# MBC5_1-3_multi.net
KiCad netlist of a schematic drawn in EAGLE
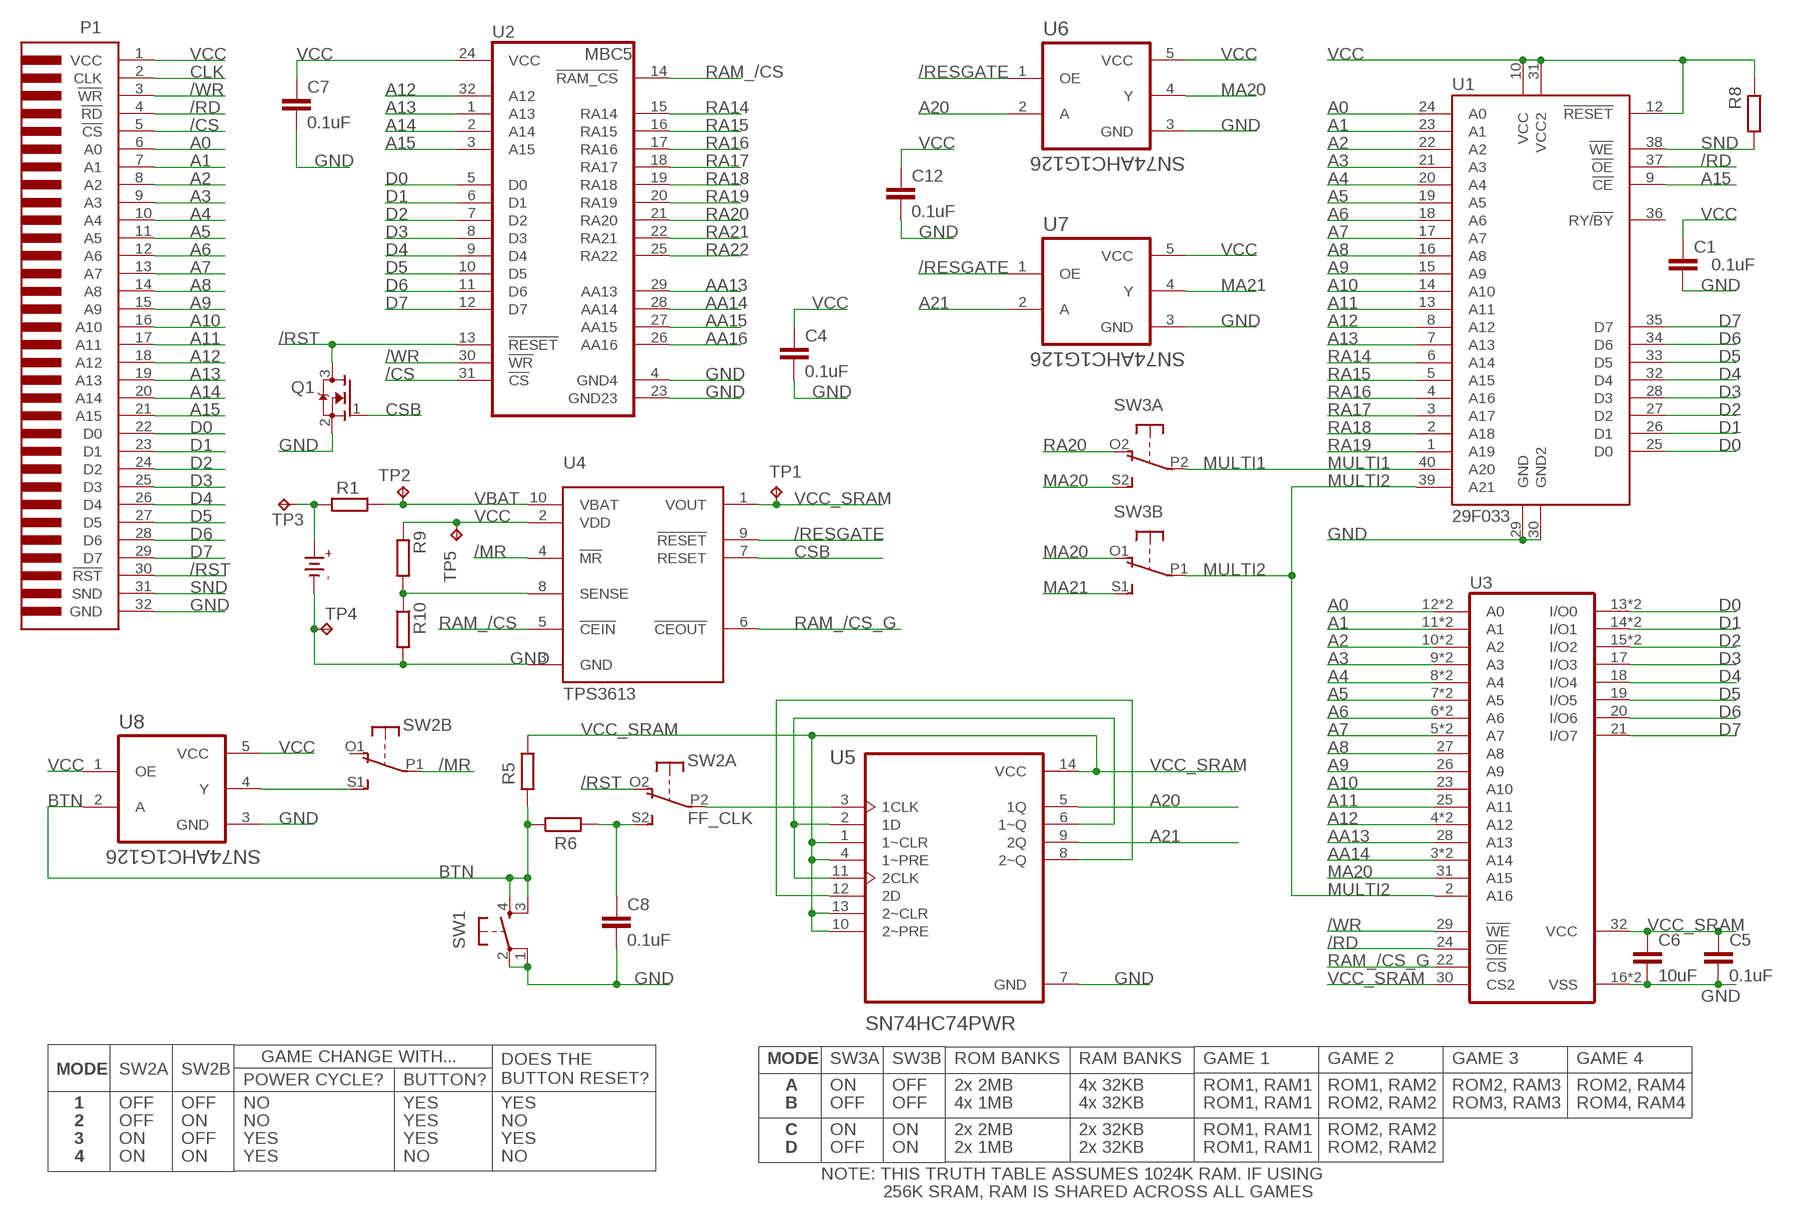
[diagram p0: schematic, sheet 1]

(export (version "E")
  (design (tool "Eeschema 10.0.6"))
  (components
    (comp (ref "C1")
      (value "0.1uF")
      (footprint "eagle-import:C0603")
      (libsource (lib "eagle-import") (part "C-EUC0603"))
    )
    (comp (ref "C4")
      (value "0.1uF")
      (footprint "eagle-import:C0603")
      (libsource (lib "eagle-import") (part "C-EUC0603"))
    )
    (comp (ref "C5")
      (value "0.1uF")
      (footprint "eagle-import:C0603")
      (libsource (lib "eagle-import") (part "C-EUC0603"))
    )
    (comp (ref "C6")
      (value "10uF")
      (footprint "eagle-import:C0603")
      (libsource (lib "eagle-import") (part "C-EUC0603"))
    )
    (comp (ref "C7")
      (value "0.1uF")
      (footprint "eagle-import:C0603")
      (libsource (lib "eagle-import") (part "C-EUC0603"))
    )
    (comp (ref "C8")
      (value "0.1uF")
      (footprint "eagle-import:C0603")
      (libsource (lib "eagle-import") (part "C-EUC0603"))
    )
    (comp (ref "C12")
      (value "0.1uF")
      (footprint "eagle-import:C0603")
      (libsource (lib "eagle-import") (part "C-EUC0603"))
    )
    (comp (ref "P1")
      (value "GBC_CARTTAB")
      (footprint "eagle-import:GBC_CART_TABBED")
      (libsource (lib "eagle-import") (part "GBC_CARTTAB"))
    )
    (comp (ref "Q1")
      (value "2N7002")
      (footprint "eagle-import:SOT23")
      (libsource (lib "eagle-import") (part "MOSFET-NREFLOW"))
    )
    (comp (ref "R1")
      (value "RR0603")
      (footprint "eagle-import:R0603")
      (libsource (lib "eagle-import") (part "RR0603"))
    )
    (comp (ref "R5")
      (value "RR0603")
      (footprint "eagle-import:R0603")
      (libsource (lib "eagle-import") (part "RR0603"))
    )
    (comp (ref "R6")
      (value "RR0603")
      (footprint "eagle-import:R0603")
      (libsource (lib "eagle-import") (part "RR0603"))
    )
    (comp (ref "R8")
      (value "RR0603")
      (footprint "eagle-import:R0603")
      (libsource (lib "eagle-import") (part "RR0603"))
    )
    (comp (ref "R9")
      (value "RR0603")
      (footprint "eagle-import:R0603")
      (libsource (lib "eagle-import") (part "RR0603"))
    )
    (comp (ref "R10")
      (value "RR0603")
      (footprint "eagle-import:R0603")
      (libsource (lib "eagle-import") (part "RR0603"))
    )
    (comp (ref "SW1")
      (value "SPST_TACT-KMR2")
      (footprint "eagle-import:KMR2")
      (libsource (lib "eagle-import") (part "SPST_TACT-KMR2"))
    )
    (comp (ref "SW2")
      (value "SPDT-2S")
      (footprint "eagle-import:CAS-D20A")
      (libsource (lib "eagle-import") (part "SPDT-2S"))
    )
    (comp (ref "SW3")
      (value "SPDT-2S")
      (footprint "eagle-import:CAS-D20A")
      (libsource (lib "eagle-import") (part "SPDT-2S"))
    )
    (comp (ref "TP1")
      (value "TPB1,27")
      (footprint "eagle-import:B1,27")
      (libsource (lib "eagle-import") (part "TPB1,27"))
    )
    (comp (ref "TP2")
      (value "TPB1,27")
      (footprint "eagle-import:B1,27")
      (libsource (lib "eagle-import") (part "TPB1,27"))
    )
    (comp (ref "TP3")
      (value "TPB1,27")
      (footprint "eagle-import:B1,27")
      (libsource (lib "eagle-import") (part "TPB1,27"))
    )
    (comp (ref "TP4")
      (value "TPB1,27")
      (footprint "eagle-import:B1,27")
      (libsource (lib "eagle-import") (part "TPB1,27"))
    )
    (comp (ref "TP5")
      (value "TPB1,27")
      (footprint "eagle-import:B1,27")
      (libsource (lib "eagle-import") (part "TPB1,27"))
    )
    (comp (ref "U$7")
      (value "CR2025")
      (footprint "eagle-import:CR2025")
      (libsource (lib "eagle-import") (part "CR2025"))
    )
    (comp (ref "U1")
      (value "29F033")
      (footprint "eagle-import:TSOP-40")
      (libsource (lib "eagle-import") (part "29F033"))
    )
    (comp (ref "U2")
      (value "MBC5")
      (footprint "eagle-import:QFP-32")
      (libsource (lib "eagle-import") (part "MBC5"))
    )
    (comp (ref "U3")
      (value "1008_62256_SRAM")
      (footprint "eagle-import:SOP-32L")
      (libsource (lib "eagle-import") (part "1008_62256_SRAM"))
    )
    (comp (ref "U4")
      (value "TPS3613")
      (footprint "eagle-import:MSOP-10")
      (libsource (lib "eagle-import") (part "TPS3613"))
    )
    (comp (ref "U5")
      (value "SN74HC74PWR")
      (footprint "eagle-import:SOP65P640X120-14N")
      (fields (field (name "MF") "Texas Instruments"))
      (libsource (lib "eagle-import") (part "SN74HC74PWR"))
    )
    (comp (ref "U6")
      (value "SN74AHC1G126")
      (footprint "eagle-import:SC70")
      (libsource (lib "eagle-import") (part "SN74AHC1G126"))
    )
    (comp (ref "U7")
      (value "SN74AHC1G126")
      (footprint "eagle-import:SC70")
      (libsource (lib "eagle-import") (part "SN74AHC1G126"))
    )
    (comp (ref "U8")
      (value "SN74AHC1G126")
      (footprint "eagle-import:SC70")
      (libsource (lib "eagle-import") (part "SN74AHC1G126"))
    )
  )
  (nets
    (net (code "1") (name "/A0") (class "Default")
      (node (ref "P1") (pin "6") (pinfunction "A0_6") (pintype "output"))
      (node (ref "U1") (pin "24") (pinfunction "A0_24") (pintype "input"))
      (node (ref "U3") (pin "12") (pinfunction "A0_12") (pintype "input"))
      (node (ref "U3") (pin "L12") (pinfunction "A0_L12") (pintype "input"))
    )
    (net (code "2") (name "/A1") (class "Default")
      (node (ref "P1") (pin "7") (pinfunction "A1_7") (pintype "output"))
      (node (ref "U1") (pin "23") (pinfunction "A1_23") (pintype "input"))
      (node (ref "U3") (pin "11") (pinfunction "A1_11") (pintype "input"))
      (node (ref "U3") (pin "L11") (pinfunction "A1_L11") (pintype "input"))
    )
    (net (code "3") (name "/A2") (class "Default")
      (node (ref "P1") (pin "8") (pinfunction "A2_8") (pintype "output"))
      (node (ref "U1") (pin "22") (pinfunction "A2_22") (pintype "input"))
      (node (ref "U3") (pin "10") (pinfunction "A2_10") (pintype "input"))
      (node (ref "U3") (pin "L10") (pinfunction "A2_L10") (pintype "input"))
    )
    (net (code "4") (name "/A3") (class "Default")
      (node (ref "P1") (pin "9") (pinfunction "A3_9") (pintype "output"))
      (node (ref "U1") (pin "21") (pinfunction "A3_21") (pintype "input"))
      (node (ref "U3") (pin "9") (pinfunction "A3_9") (pintype "input"))
      (node (ref "U3") (pin "L9") (pinfunction "A3_L9") (pintype "input"))
    )
    (net (code "5") (name "/A4") (class "Default")
      (node (ref "P1") (pin "10") (pinfunction "A4_10") (pintype "output"))
      (node (ref "U1") (pin "20") (pinfunction "A4_20") (pintype "input"))
      (node (ref "U3") (pin "8") (pinfunction "A4_8") (pintype "input"))
      (node (ref "U3") (pin "L8") (pinfunction "A4_L8") (pintype "input"))
    )
    (net (code "6") (name "/A5") (class "Default")
      (node (ref "P1") (pin "11") (pinfunction "A5_11") (pintype "output"))
      (node (ref "U1") (pin "19") (pinfunction "A5_19") (pintype "input"))
      (node (ref "U3") (pin "7") (pinfunction "A5_7") (pintype "input"))
      (node (ref "U3") (pin "L7") (pinfunction "A5_L7") (pintype "input"))
    )
    (net (code "7") (name "/A6") (class "Default")
      (node (ref "P1") (pin "12") (pinfunction "A6_12") (pintype "output"))
      (node (ref "U1") (pin "18") (pinfunction "A6_18") (pintype "input"))
      (node (ref "U3") (pin "6") (pinfunction "A6_6") (pintype "input"))
      (node (ref "U3") (pin "L6") (pinfunction "A6_L6") (pintype "input"))
    )
    (net (code "8") (name "/A7") (class "Default")
      (node (ref "P1") (pin "13") (pinfunction "A7_13") (pintype "output"))
      (node (ref "U1") (pin "17") (pinfunction "A7_17") (pintype "input"))
      (node (ref "U3") (pin "5") (pinfunction "A7_5") (pintype "input"))
      (node (ref "U3") (pin "L5") (pinfunction "A7_L5") (pintype "input"))
    )
    (net (code "9") (name "/A8") (class "Default")
      (node (ref "P1") (pin "14") (pinfunction "A8_14") (pintype "output"))
      (node (ref "U1") (pin "16") (pinfunction "A8_16") (pintype "input"))
      (node (ref "U3") (pin "27") (pinfunction "A8_27") (pintype "input"))
    )
    (net (code "10") (name "/A9") (class "Default")
      (node (ref "P1") (pin "15") (pinfunction "A9_15") (pintype "output"))
      (node (ref "U1") (pin "15") (pinfunction "A9_15") (pintype "input"))
      (node (ref "U3") (pin "26") (pinfunction "A9_26") (pintype "input"))
    )
    (net (code "11") (name "/A10") (class "Default")
      (node (ref "P1") (pin "16") (pinfunction "A10_16") (pintype "output"))
      (node (ref "U1") (pin "14") (pinfunction "A10_14") (pintype "input"))
      (node (ref "U3") (pin "23") (pinfunction "A10_23") (pintype "input"))
    )
    (net (code "12") (name "/A11") (class "Default")
      (node (ref "P1") (pin "17") (pinfunction "A11_17") (pintype "output"))
      (node (ref "U1") (pin "13") (pinfunction "A11_13") (pintype "input"))
      (node (ref "U3") (pin "25") (pinfunction "A11_25") (pintype "input"))
    )
    (net (code "13") (name "/A12") (class "Default")
      (node (ref "P1") (pin "18") (pinfunction "A12_18") (pintype "output"))
      (node (ref "U1") (pin "8") (pinfunction "A12_8") (pintype "input"))
      (node (ref "U2") (pin "32") (pinfunction "A12_32") (pintype "input"))
      (node (ref "U3") (pin "4") (pinfunction "A12_4") (pintype "input"))
      (node (ref "U3") (pin "L4") (pinfunction "A12_L4") (pintype "input"))
    )
    (net (code "14") (name "/A13") (class "Default")
      (node (ref "P1") (pin "19") (pinfunction "A13_19") (pintype "output"))
      (node (ref "U1") (pin "7") (pinfunction "A13_7") (pintype "input"))
      (node (ref "U2") (pin "1") (pinfunction "A13_1") (pintype "input"))
    )
    (net (code "15") (name "/A14") (class "Default")
      (node (ref "P1") (pin "20") (pinfunction "A14_20") (pintype "output"))
      (node (ref "U2") (pin "2") (pinfunction "A14_2") (pintype "input"))
    )
    (net (code "16") (name "/A15") (class "Default")
      (node (ref "P1") (pin "21") (pinfunction "A15_21") (pintype "output"))
      (node (ref "U1") (pin "9") (pinfunction "~{CE}_9") (pintype "input"))
      (node (ref "U2") (pin "3") (pinfunction "A15_3") (pintype "input"))
    )
    (net (code "17") (name "/A20") (class "Default")
      (node (ref "U5") (pin "5") (pinfunction "1Q_5") (pintype "output"))
      (node (ref "U6") (pin "2") (pinfunction "A_2") (pintype "input"))
    )
    (net (code "18") (name "/A21") (class "Default")
      (node (ref "U5") (pin "9") (pinfunction "2Q_9") (pintype "output"))
      (node (ref "U7") (pin "2") (pinfunction "A_2") (pintype "input"))
    )
    (net (code "19") (name "/AA13") (class "Default")
      (node (ref "U2") (pin "29") (pinfunction "AA13_29") (pintype "output"))
      (node (ref "U3") (pin "28") (pinfunction "A13_28") (pintype "input"))
    )
    (net (code "20") (name "/AA14") (class "Default")
      (node (ref "U2") (pin "28") (pinfunction "AA14_28") (pintype "output"))
      (node (ref "U3") (pin "3") (pinfunction "A14_3") (pintype "input"))
      (node (ref "U3") (pin "L3") (pinfunction "A14_L3") (pintype "input"))
    )
    (net (code "21") (name "/AA15") (class "Default")
      (node (ref "U2") (pin "27") (pinfunction "AA15_27") (pintype "output"))
    )
    (net (code "22") (name "/AA16") (class "Default")
      (node (ref "U2") (pin "26") (pinfunction "AA16_26") (pintype "output"))
    )
    (net (code "23") (name "/BTN") (class "Default")
      (node (ref "R5") (pin "2") (pinfunction "2_2") (pintype "passive"))
      (node (ref "R6") (pin "1") (pinfunction "1_1") (pintype "passive"))
      (node (ref "SW1") (pin "3") (pinfunction "S1_3") (pintype "passive"))
      (node (ref "SW1") (pin "4") (pinfunction "S_4") (pintype "passive"))
      (node (ref "U8") (pin "2") (pinfunction "A_2") (pintype "input"))
    )
    (net (code "24") (name "/CLK") (class "Default")
      (node (ref "P1") (pin "2") (pinfunction "CLK_2") (pintype "output"))
    )
    (net (code "25") (name "/CSB") (class "Default")
      (node (ref "Q1") (pin "1") (pinfunction "G_1") (pintype "bidirectional"))
      (node (ref "U4") (pin "7") (pinfunction "RESET_7") (pintype "output"))
    )
    (net (code "26") (name "/D0") (class "Default")
      (node (ref "P1") (pin "22") (pinfunction "D0_22") (pintype "bidirectional"))
      (node (ref "U1") (pin "25") (pinfunction "D0_25") (pintype "bidirectional"))
      (node (ref "U2") (pin "5") (pinfunction "D0_5") (pintype "input"))
      (node (ref "U3") (pin "13") (pinfunction "I/O0_13") (pintype "bidirectional"))
      (node (ref "U3") (pin "L13") (pinfunction "I/O0_L13") (pintype "bidirectional"))
    )
    (net (code "27") (name "/D1") (class "Default")
      (node (ref "P1") (pin "23") (pinfunction "D1_23") (pintype "bidirectional"))
      (node (ref "U1") (pin "26") (pinfunction "D1_26") (pintype "bidirectional"))
      (node (ref "U2") (pin "6") (pinfunction "D1_6") (pintype "input"))
      (node (ref "U3") (pin "14") (pinfunction "I/O1_14") (pintype "bidirectional"))
      (node (ref "U3") (pin "L14") (pinfunction "I/O1_L14") (pintype "bidirectional"))
    )
    (net (code "28") (name "/D2") (class "Default")
      (node (ref "P1") (pin "24") (pinfunction "D2_24") (pintype "bidirectional"))
      (node (ref "U1") (pin "27") (pinfunction "D2_27") (pintype "bidirectional"))
      (node (ref "U2") (pin "7") (pinfunction "D2_7") (pintype "input"))
      (node (ref "U3") (pin "15") (pinfunction "I/O2_15") (pintype "bidirectional"))
      (node (ref "U3") (pin "L15") (pinfunction "I/O2_L15") (pintype "bidirectional"))
    )
    (net (code "29") (name "/D3") (class "Default")
      (node (ref "P1") (pin "25") (pinfunction "D3_25") (pintype "bidirectional"))
      (node (ref "U1") (pin "28") (pinfunction "D3_28") (pintype "bidirectional"))
      (node (ref "U2") (pin "8") (pinfunction "D3_8") (pintype "input"))
      (node (ref "U3") (pin "17") (pinfunction "I/O3_17") (pintype "bidirectional"))
    )
    (net (code "30") (name "/D4") (class "Default")
      (node (ref "P1") (pin "26") (pinfunction "D4_26") (pintype "bidirectional"))
      (node (ref "U1") (pin "32") (pinfunction "D4_32") (pintype "bidirectional"))
      (node (ref "U2") (pin "9") (pinfunction "D4_9") (pintype "input"))
      (node (ref "U3") (pin "18") (pinfunction "I/O4_18") (pintype "bidirectional"))
    )
    (net (code "31") (name "/D5") (class "Default")
      (node (ref "P1") (pin "27") (pinfunction "D5_27") (pintype "bidirectional"))
      (node (ref "U1") (pin "33") (pinfunction "D5_33") (pintype "bidirectional"))
      (node (ref "U2") (pin "10") (pinfunction "D5_10") (pintype "input"))
      (node (ref "U3") (pin "19") (pinfunction "I/O5_19") (pintype "bidirectional"))
    )
    (net (code "32") (name "/D6") (class "Default")
      (node (ref "P1") (pin "28") (pinfunction "D6_28") (pintype "bidirectional"))
      (node (ref "U1") (pin "34") (pinfunction "D6_34") (pintype "bidirectional"))
      (node (ref "U2") (pin "11") (pinfunction "D6_11") (pintype "input"))
      (node (ref "U3") (pin "20") (pinfunction "I/O6_20") (pintype "bidirectional"))
    )
    (net (code "33") (name "/D7") (class "Default")
      (node (ref "P1") (pin "29") (pinfunction "D7_29") (pintype "bidirectional"))
      (node (ref "U1") (pin "35") (pinfunction "D7_35") (pintype "bidirectional"))
      (node (ref "U2") (pin "12") (pinfunction "D7_12") (pintype "input"))
      (node (ref "U3") (pin "21") (pinfunction "I/O7_21") (pintype "bidirectional"))
    )
    (net (code "34") (name "/FF_CLK") (class "Default")
      (node (ref "SW2") (pin "P2") (pinfunction "P_P2") (pintype "passive"))
      (node (ref "U5") (pin "3") (pinfunction "1CLK_3") (pintype "input"))
    )
    (net (code "35") (name "/GND") (class "Default")
      (node (ref "C1") (pin "2") (pinfunction "2_2") (pintype "passive"))
      (node (ref "C12") (pin "2") (pinfunction "2_2") (pintype "passive"))
      (node (ref "C4") (pin "2") (pinfunction "2_2") (pintype "passive"))
      (node (ref "C5") (pin "2") (pinfunction "2_2") (pintype "passive"))
      (node (ref "C6") (pin "2") (pinfunction "2_2") (pintype "passive"))
      (node (ref "C7") (pin "2") (pinfunction "2_2") (pintype "passive"))
      (node (ref "C8") (pin "2") (pinfunction "2_2") (pintype "passive"))
      (node (ref "P1") (pin "32") (pinfunction "GND_32") (pintype "power_in"))
      (node (ref "Q1") (pin "2") (pinfunction "S_2") (pintype "bidirectional"))
      (node (ref "R10") (pin "2") (pinfunction "2_2") (pintype "passive"))
      (node (ref "SW1") (pin "1") (pinfunction "P1_1") (pintype "passive"))
      (node (ref "SW1") (pin "2") (pinfunction "P_2") (pintype "passive"))
      (node (ref "TP4") (pin "TP") (pinfunction "TP_TP") (pintype "input"))
      (node (ref "U$7") (pin "-") (pinfunction "-_-") (pintype "power_in"))
      (node (ref "U1") (pin "29") (pinfunction "GND_29") (pintype "power_in"))
      (node (ref "U1") (pin "30") (pinfunction "GND2_30") (pintype "power_in"))
      (node (ref "U2") (pin "23") (pinfunction "GND23_23") (pintype "power_in"))
      (node (ref "U2") (pin "4") (pinfunction "GND4_4") (pintype "power_in"))
      (node (ref "U3") (pin "16") (pinfunction "VSS_16") (pintype "power_in"))
      (node (ref "U3") (pin "L16") (pinfunction "VSS_L16") (pintype "power_in"))
      (node (ref "U4") (pin "3") (pinfunction "GND_3") (pintype "power_in"))
      (node (ref "U5") (pin "7") (pinfunction "GND_7") (pintype "power_in"))
      (node (ref "U6") (pin "3") (pinfunction "GND_3") (pintype "power_in"))
      (node (ref "U7") (pin "3") (pinfunction "GND_3") (pintype "power_in"))
      (node (ref "U8") (pin "3") (pinfunction "GND_3") (pintype "power_in"))
    )
    (net (code "36") (name "/MA20") (class "Default")
      (node (ref "SW3") (pin "O1") (pinfunction "O_O1") (pintype "passive"))
      (node (ref "SW3") (pin "S2") (pinfunction "S_S2") (pintype "passive"))
      (node (ref "U3") (pin "31") (pinfunction "A15_31") (pintype "input"))
      (node (ref "U6") (pin "4") (pinfunction "Y_4") (pintype "output"))
    )
    (net (code "37") (name "/MA21") (class "Default")
      (node (ref "SW3") (pin "S1") (pinfunction "S_S1") (pintype "passive"))
      (node (ref "U7") (pin "4") (pinfunction "Y_4") (pintype "output"))
    )
    (net (code "38") (name "/MULTI1") (class "Default")
      (node (ref "SW3") (pin "P2") (pinfunction "P_P2") (pintype "passive"))
      (node (ref "U1") (pin "40") (pinfunction "A20_40") (pintype "input"))
    )
    (net (code "39") (name "/MULTI2") (class "Default")
      (node (ref "SW3") (pin "P1") (pinfunction "P_P1") (pintype "passive"))
      (node (ref "U1") (pin "39") (pinfunction "A21_39") (pintype "input"))
      (node (ref "U3") (pin "2") (pinfunction "A16_2") (pintype "input"))
    )
    (net (code "40") (name "/RA14") (class "Default")
      (node (ref "U1") (pin "6") (pinfunction "A14_6") (pintype "input"))
      (node (ref "U2") (pin "15") (pinfunction "RA14_15") (pintype "output"))
    )
    (net (code "41") (name "/RA15") (class "Default")
      (node (ref "U1") (pin "5") (pinfunction "A15_5") (pintype "input"))
      (node (ref "U2") (pin "16") (pinfunction "RA15_16") (pintype "output"))
    )
    (net (code "42") (name "/RA16") (class "Default")
      (node (ref "U1") (pin "4") (pinfunction "A16_4") (pintype "input"))
      (node (ref "U2") (pin "17") (pinfunction "RA16_17") (pintype "output"))
    )
    (net (code "43") (name "/RA17") (class "Default")
      (node (ref "U1") (pin "3") (pinfunction "A17_3") (pintype "input"))
      (node (ref "U2") (pin "18") (pinfunction "RA17_18") (pintype "output"))
    )
    (net (code "44") (name "/RA18") (class "Default")
      (node (ref "U1") (pin "2") (pinfunction "A18_2") (pintype "input"))
      (node (ref "U2") (pin "19") (pinfunction "RA18_19") (pintype "output"))
    )
    (net (code "45") (name "/RA19") (class "Default")
      (node (ref "U1") (pin "1") (pinfunction "A19_1") (pintype "input"))
      (node (ref "U2") (pin "20") (pinfunction "RA19_20") (pintype "output"))
    )
    (net (code "46") (name "/RA20") (class "Default")
      (node (ref "SW3") (pin "O2") (pinfunction "O_O2") (pintype "passive"))
      (node (ref "U2") (pin "21") (pinfunction "RA20_21") (pintype "output"))
    )
    (net (code "47") (name "/RA21") (class "Default")
      (node (ref "U2") (pin "22") (pinfunction "RA21_22") (pintype "output"))
    )
    (net (code "48") (name "/RA22") (class "Default")
      (node (ref "U2") (pin "25") (pinfunction "RA22_25") (pintype "output"))
    )
    (net (code "49") (name "/RAM_{slash}CS") (class "Default")
      (node (ref "U2") (pin "14") (pinfunction "~{RAM_CS}_14") (pintype "output"))
      (node (ref "U4") (pin "5") (pinfunction "~{CEIN}_5") (pintype "input"))
    )
    (net (code "50") (name "/RAM_{slash}CS_G") (class "Default")
      (node (ref "U3") (pin "22") (pinfunction "~{CS}_22") (pintype "input"))
      (node (ref "U4") (pin "6") (pinfunction "~{CEOUT}_6") (pintype "output"))
    )
    (net (code "51") (name "/SND") (class "Default")
      (node (ref "P1") (pin "31") (pinfunction "SND_31") (pintype "bidirectional"))
      (node (ref "R8") (pin "2") (pinfunction "2_2") (pintype "passive"))
      (node (ref "U1") (pin "38") (pinfunction "~{WE}_38") (pintype "input"))
    )
    (net (code "52") (name "/VBAT") (class "Default")
      (node (ref "R1") (pin "1") (pinfunction "1_1") (pintype "passive"))
      (node (ref "TP2") (pin "TP") (pinfunction "TP_TP") (pintype "input"))
      (node (ref "U4") (pin "10") (pinfunction "VBAT_10") (pintype "power_in"))
    )
    (net (code "53") (name "/VCC") (class "Default")
      (node (ref "C1") (pin "1") (pinfunction "1_1") (pintype "passive"))
      (node (ref "C12") (pin "1") (pinfunction "1_1") (pintype "passive"))
      (node (ref "C4") (pin "1") (pinfunction "1_1") (pintype "passive"))
      (node (ref "C7") (pin "1") (pinfunction "1_1") (pintype "passive"))
      (node (ref "P1") (pin "1") (pinfunction "VCC_1") (pintype "power_in"))
      (node (ref "R8") (pin "1") (pinfunction "1_1") (pintype "passive"))
      (node (ref "R9") (pin "1") (pinfunction "1_1") (pintype "passive"))
      (node (ref "TP5") (pin "TP") (pinfunction "TP_TP") (pintype "input"))
      (node (ref "U1") (pin "10") (pinfunction "VCC_10") (pintype "power_in"))
      (node (ref "U1") (pin "12") (pinfunction "~{RESET}_12") (pintype "input"))
      (node (ref "U1") (pin "31") (pinfunction "VCC2_31") (pintype "power_in"))
      (node (ref "U2") (pin "24") (pinfunction "VCC_24") (pintype "power_in"))
      (node (ref "U4") (pin "2") (pinfunction "VDD_2") (pintype "power_in"))
      (node (ref "U6") (pin "5") (pinfunction "VCC_5") (pintype "power_in"))
      (node (ref "U7") (pin "5") (pinfunction "VCC_5") (pintype "power_in"))
      (node (ref "U8") (pin "1") (pinfunction "OE_1") (pintype "input"))
      (node (ref "U8") (pin "5") (pinfunction "VCC_5") (pintype "power_in"))
    )
    (net (code "54") (name "/VCC_SRAM") (class "Default")
      (node (ref "C5") (pin "1") (pinfunction "1_1") (pintype "passive"))
      (node (ref "C6") (pin "1") (pinfunction "1_1") (pintype "passive"))
      (node (ref "R5") (pin "1") (pinfunction "1_1") (pintype "passive"))
      (node (ref "TP1") (pin "TP") (pinfunction "TP_TP") (pintype "input"))
      (node (ref "U3") (pin "30") (pinfunction "CS2_30") (pintype "input"))
      (node (ref "U3") (pin "32") (pinfunction "VCC_32") (pintype "power_in"))
      (node (ref "U4") (pin "1") (pinfunction "VOUT_1") (pintype "power_in"))
      (node (ref "U5") (pin "1") (pinfunction "1~{CLR}_1") (pintype "input"))
      (node (ref "U5") (pin "10") (pinfunction "2~{PRE}_10") (pintype "input"))
      (node (ref "U5") (pin "13") (pinfunction "2~{CLR}_13") (pintype "input"))
      (node (ref "U5") (pin "14") (pinfunction "VCC_14") (pintype "power_in"))
      (node (ref "U5") (pin "4") (pinfunction "1~{PRE}_4") (pintype "input"))
    )
    (net (code "55") (name "/{slash}CS") (class "Default")
      (node (ref "P1") (pin "5") (pinfunction "~{CS}_5") (pintype "output"))
      (node (ref "U2") (pin "31") (pinfunction "~{CS}_31") (pintype "input"))
    )
    (net (code "56") (name "/{slash}MR") (class "Default")
      (node (ref "SW2") (pin "P1") (pinfunction "P_P1") (pintype "passive"))
      (node (ref "U4") (pin "4") (pinfunction "~{MR}_4") (pintype "input"))
    )
    (net (code "57") (name "/{slash}RD") (class "Default")
      (node (ref "P1") (pin "4") (pinfunction "~{RD}_4") (pintype "output"))
      (node (ref "U1") (pin "37") (pinfunction "~{OE}_37") (pintype "input"))
      (node (ref "U3") (pin "24") (pinfunction "~{OE}_24") (pintype "input"))
    )
    (net (code "58") (name "/{slash}RESGATE") (class "Default")
      (node (ref "U4") (pin "9") (pinfunction "~{RESET}_9") (pintype "output"))
      (node (ref "U6") (pin "1") (pinfunction "OE_1") (pintype "input"))
      (node (ref "U7") (pin "1") (pinfunction "OE_1") (pintype "input"))
    )
    (net (code "59") (name "/{slash}RST") (class "Default")
      (node (ref "P1") (pin "30") (pinfunction "~{RST}_30") (pintype "bidirectional"))
      (node (ref "Q1") (pin "3") (pinfunction "D_3") (pintype "bidirectional"))
      (node (ref "SW2") (pin "O2") (pinfunction "O_O2") (pintype "passive"))
      (node (ref "U2") (pin "13") (pinfunction "~{RESET}_13") (pintype "input"))
    )
    (net (code "60") (name "/{slash}WR") (class "Default")
      (node (ref "P1") (pin "3") (pinfunction "~{WR}_3") (pintype "output"))
      (node (ref "U2") (pin "30") (pinfunction "~{WR}_30") (pintype "input"))
      (node (ref "U3") (pin "29") (pinfunction "~{WE}_29") (pintype "input"))
    )
    (net (code "61") (name "Net-(R1-Pad2)") (class "Default")
      (node (ref "R1") (pin "2") (pinfunction "2_2") (pintype "passive"))
      (node (ref "TP3") (pin "TP") (pinfunction "TP_TP") (pintype "input"))
      (node (ref "U$7") (pin "+") (pinfunction "+_+") (pintype "power_in"))
    )
    (net (code "62") (name "Net-(SW2A-S)") (class "Default")
      (node (ref "SW2") (pin "S1") (pinfunction "S_S1") (pintype "passive"))
      (node (ref "U8") (pin "4") (pinfunction "Y_4") (pintype "output"))
    )
    (net (code "63") (name "Net-(SW2B-S)") (class "Default")
      (node (ref "C8") (pin "1") (pinfunction "1_1") (pintype "passive"))
      (node (ref "R6") (pin "2") (pinfunction "2_2") (pintype "passive"))
      (node (ref "SW2") (pin "S2") (pinfunction "S_S2") (pintype "passive"))
    )
    (net (code "64") (name "Net-(U4-SENSE)") (class "Default")
      (node (ref "R10") (pin "1") (pinfunction "1_1") (pintype "passive"))
      (node (ref "R9") (pin "2") (pinfunction "2_2") (pintype "passive"))
      (node (ref "U4") (pin "8") (pinfunction "SENSE_8") (pintype "input"))
    )
    (net (code "65") (name "Net-(U5-1D)") (class "Default")
      (node (ref "U5") (pin "11") (pinfunction "2CLK_11") (pintype "input"))
      (node (ref "U5") (pin "2") (pinfunction "1D_2") (pintype "input"))
      (node (ref "U5") (pin "6") (pinfunction "1~{Q}_6") (pintype "output"))
    )
    (net (code "66") (name "Net-(U5-2D)") (class "Default")
      (node (ref "U5") (pin "12") (pinfunction "2D_12") (pintype "input"))
      (node (ref "U5") (pin "8") (pinfunction "2~{Q}_8") (pintype "output"))
    )
    (net (code "67") (name "unconnected-(SW2A-O-PadO1)") (class "Default")
      (node (ref "SW2") (pin "O1") (pinfunction "O_O1") (pintype "passive"))
    )
    (net (code "68") (name "unconnected-(U1-RY{slash}~{BY}-Pad36)") (class "Default")
      (node (ref "U1") (pin "36") (pinfunction "RY/~{BY}_36") (pintype "output"))
    )
  )
)
